# THS3201.net
KiCad netlist of a schematic drawn in Altium Designer
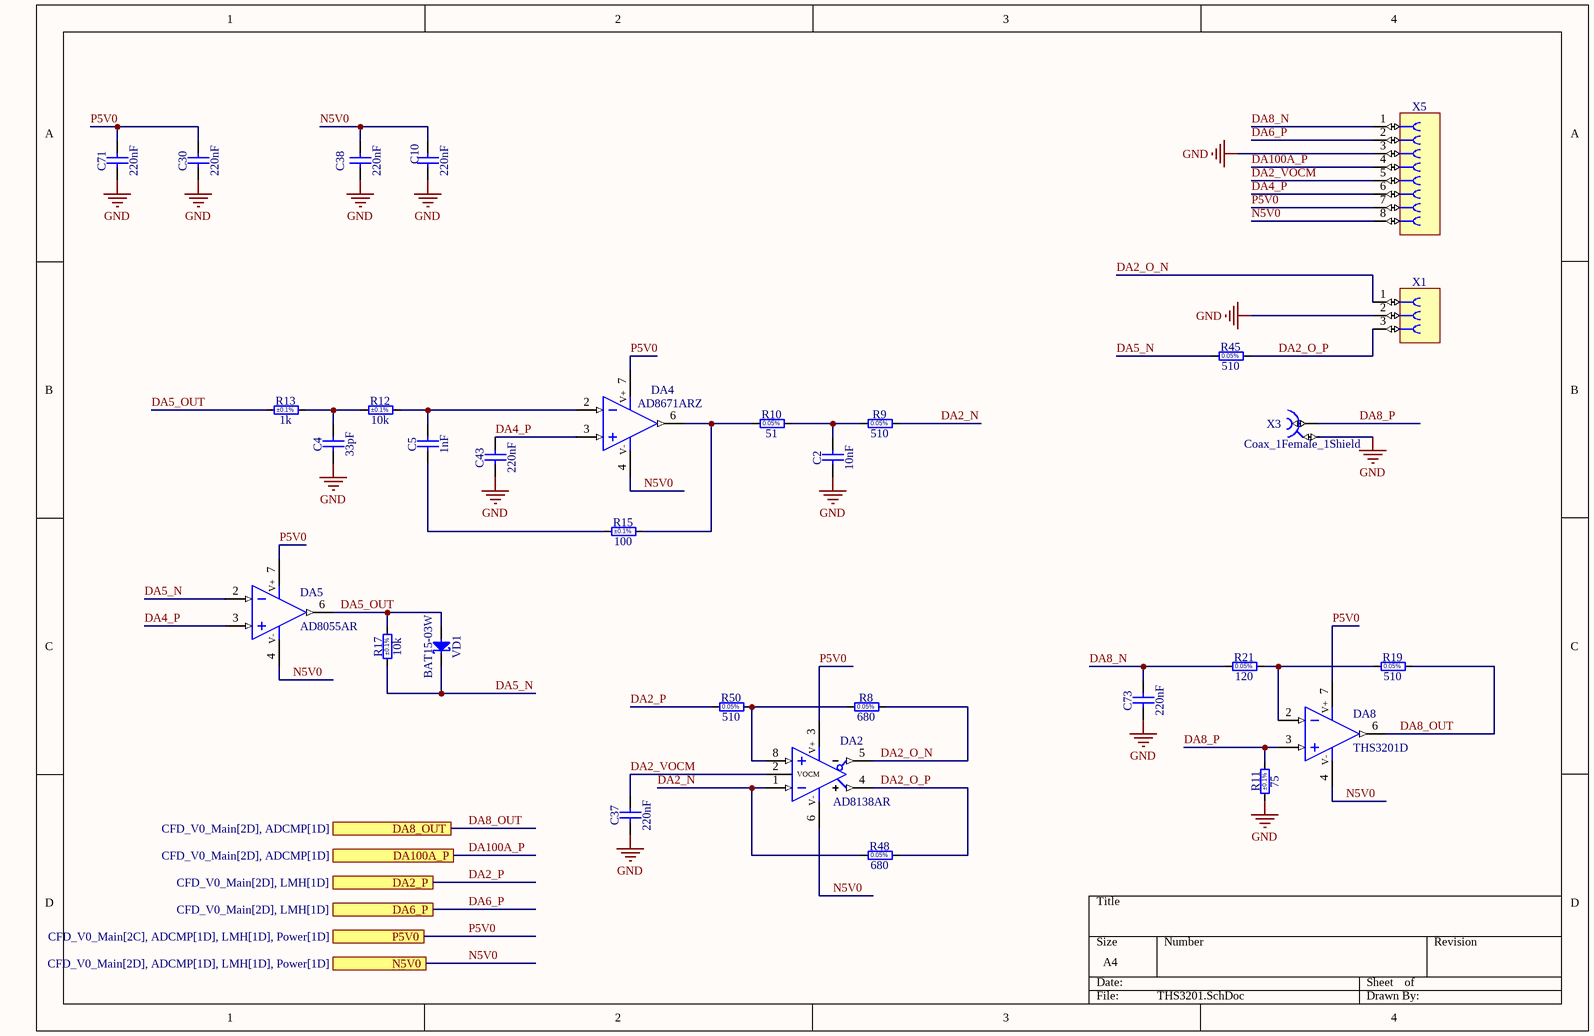
[diagram p0: THS3201.SchDoc]

(export (version "E")
  (design (tool "Eeschema 10.0.6"))
  (components
    (comp (ref "C2")
      (value "10nF")
      (footprint "CAPC2012X135N")
      (description "Non-polarised capacitor")
      (fields
        (field (name "PART NUMBER") "CC0805_10NF_50V_2%_C0G")
        (field (name "VOLTAGE") "50V")
        (field (name "AUTHOR") "CERN DEM HF")
      )
      (libsource (lib "Capacitors") (part "Capacitor - non polarized"))
    )
    (comp (ref "C4")
      (value "33pF")
      (footprint "CAPC2013X115N")
      (description "Non-polarised capacitor")
      (fields
        (field (name "PART NUMBER") "CC0805_33PF_200V_1%_NP0")
        (field (name "VOLTAGE") "200V")
        (field (name "AUTHOR") "CERN DEM HF")
      )
      (libsource (lib "Capacitors") (part "Capacitor - non polarized"))
    )
    (comp (ref "C5")
      (value "1nF")
      (footprint "CAPC2013X100N")
      (description "Non-polarised capacitor")
      (fields
        (field (name "PART NUMBER") "CC0805_1NF_25V_1%_C0G")
        (field (name "VOLTAGE") "25V")
        (field (name "AUTHOR") "CERN DEM JLC")
      )
      (libsource (lib "Capacitors") (part "Capacitor - non polarized"))
    )
    (comp (ref "C10")
      (value "220nF")
      (footprint "CAPC2012X135N")
      (description "Non-polarised capacitor")
      (fields
        (field (name "PART NUMBER") "CC0805_220NF_50V_10%_X7R")
        (field (name "VOLTAGE") "50V")
        (field (name "AUTHOR") "CERN DEM JLC")
      )
      (libsource (lib "Capacitors") (part "Capacitor - non polarized"))
    )
    (comp (ref "C30")
      (value "220nF")
      (footprint "CAPC2012X135N")
      (description "Non-polarised capacitor")
      (fields
        (field (name "PART NUMBER") "CC0805_220NF_50V_10%_X7R")
        (field (name "VOLTAGE") "50V")
        (field (name "AUTHOR") "CERN DEM JLC")
      )
      (libsource (lib "Capacitors") (part "Capacitor - non polarized"))
    )
    (comp (ref "C37")
      (value "220nF")
      (footprint "CAPC2012X135N")
      (description "Non-polarised capacitor")
      (fields
        (field (name "PART NUMBER") "CC0805_220NF_50V_10%_X7R")
        (field (name "VOLTAGE") "50V")
        (field (name "AUTHOR") "CERN DEM JLC")
      )
      (libsource (lib "Capacitors") (part "Capacitor - non polarized"))
    )
    (comp (ref "C38")
      (value "220nF")
      (footprint "CAPC2012X135N")
      (description "Non-polarised capacitor")
      (fields
        (field (name "PART NUMBER") "CC0805_220NF_50V_10%_X7R")
        (field (name "VOLTAGE") "50V")
        (field (name "AUTHOR") "CERN DEM JLC")
      )
      (libsource (lib "Capacitors") (part "Capacitor - non polarized"))
    )
    (comp (ref "C43")
      (value "220nF")
      (footprint "CAPC2012X135N")
      (description "Non-polarised capacitor")
      (fields
        (field (name "PART NUMBER") "CC0805_220NF_50V_10%_X7R")
        (field (name "VOLTAGE") "50V")
        (field (name "AUTHOR") "CERN DEM JLC")
      )
      (libsource (lib "Capacitors") (part "Capacitor - non polarized"))
    )
    (comp (ref "C71")
      (value "220nF")
      (footprint "CAPC2012X135N")
      (description "Non-polarised capacitor")
      (fields
        (field (name "PART NUMBER") "CC0805_220NF_50V_10%_X7R")
        (field (name "VOLTAGE") "50V")
        (field (name "AUTHOR") "CERN DEM JLC")
      )
      (libsource (lib "Capacitors") (part "Capacitor - non polarized"))
    )
    (comp (ref "C73")
      (value "220nF")
      (footprint "CAPC2012X135N")
      (description "Non-polarised capacitor")
      (fields
        (field (name "PART NUMBER") "CC0805_220NF_50V_10%_X7R")
        (field (name "VOLTAGE") "50V")
        (field (name "AUTHOR") "CERN DEM JLC")
      )
      (libsource (lib "Capacitors") (part "Capacitor - non polarized"))
    )
    (comp (ref "DA2")
      (value "AD8138AR")
      (footprint "SOIC127P600X175-8N")
      (description "Differential Amplifier")
      (fields (field (name "MANUFACTURER") "ANALOG DEVICES") (field (name "AUTHOR") "CERN DEM JLC"))
      (libsource (lib "ICs And Semiconductors") (part "Differential Amplifier Type1"))
    )
    (comp (ref "DA4")
      (value "AD8671ARZ")
      (footprint "SOIC127P600X175-8N")
      (description "Operational Amplifier")
      (fields
        (field (name "MANUFACTURER") "ANALOG DEVICES")
        (field (name "MANUFACTURER PART NUMBER") "AD8671AR")
        (field (name "AUTHOR") "CERN DEM JLC")
      )
      (libsource (lib "ICs And Semiconductors") (part "Operational Amplifier Type1"))
    )
    (comp (ref "DA5")
      (value "AD8055AR")
      (footprint "SOIC127P600X175-8N")
      (description "Operational Amplifier")
      (fields (field (name "MANUFACTURER") "ANALOG DEVICES") (field (name "AUTHOR") "CERN DEM HF"))
      (libsource (lib "ICs And Semiconductors") (part "Operational Amplifier Type1"))
    )
    (comp (ref "DA8")
      (value "THS3201D")
      (footprint "SOIC127P600X175-8N")
      (description "Operational Amplifier")
      (fields (field (name "MANUFACTURER") "TEXAS INSTRUMENTS") (field (name "AUTHOR") "CERN DEM HF"))
      (libsource (lib "ICs And Semiconductors") (part "Operational Amplifier Type1"))
    )
    (comp (ref "R8")
      (value "680")
      (footprint "RESC2012X60N")
      (description "Resistor - 0.05%")
      (fields
        (field (name "PART NUMBER") "R0805_680R_0.05%_0.125W_10PPM")
        (field (name "POWER") "0.1W")
        (field (name "AUTHOR") "CERN DEM HF")
      )
      (libsource (lib "Resistors") (part "Resistor - 0.05%"))
    )
    (comp (ref "R9")
      (value "510")
      (footprint "RESC1608X55N")
      (description "Resistor - 0.05%")
      (fields
        (field (name "PART NUMBER") "R0603_510R_0.1%_0.1W_10PPM")
        (field (name "POWER") "0.1W")
        (field (name "AUTHOR") "CERN DEM HF")
      )
      (libsource (lib "Resistors") (part "Resistor - 0.05%"))
    )
    (comp (ref "R10")
      (value "51")
      (footprint "RESC2012X60N")
      (description "Resistor - 0.05%")
      (fields
        (field (name "PART NUMBER") "R0805_51R_0.05%_0.125W_10PPM")
        (field (name "POWER") "0.1W")
        (field (name "AUTHOR") "CERN DEM HF")
      )
      (libsource (lib "Resistors") (part "Resistor - 0.05%"))
    )
    (comp (ref "R11")
      (value "75")
      (footprint "RESC1608X55N")
      (description "Resistor - 0.1%")
      (fields
        (field (name "TOLERANCE") "±0.1%")
        (field (name "PART NUMBER") "R0603_75R_0.1%_0.063W_10PPM")
        (field (name "POWER") "0.063W")
        (field (name "AUTHOR") "CERN DEM JLC")
      )
      (libsource (lib "Resistors") (part "Resistor - 0.1%"))
    )
    (comp (ref "R12")
      (value "10k")
      (footprint "RESC2012X60N")
      (description "Resistor - 0.1%")
      (fields
        (field (name "TOLERANCE") "±0.1%")
        (field (name "PART NUMBER") "R0805_10K_0.1%_0.1W_10PPM")
        (field (name "POWER") "0.1W")
        (field (name "AUTHOR") "CERN DEM JLC")
      )
      (libsource (lib "Resistors") (part "Resistor - 0.1%"))
    )
    (comp (ref "R13")
      (value "1k")
      (footprint "RESC2012X60N")
      (description "Resistor - 0.1%")
      (fields
        (field (name "TOLERANCE") "±0.1%")
        (field (name "PART NUMBER") "R0805_1K_0.1%_0.1W_10PPM")
        (field (name "POWER") "0.1W")
        (field (name "AUTHOR") "CERN DEM JLC")
      )
      (libsource (lib "Resistors") (part "Resistor - 0.1%"))
    )
    (comp (ref "R15")
      (value "100")
      (footprint "RESC2012X60N")
      (description "Resistor - 0.1%")
      (fields
        (field (name "TOLERANCE") "±0.1%")
        (field (name "PART NUMBER") "R0805_100R_0.1%_0.1W_10PPM")
        (field (name "POWER") "0.1W")
        (field (name "AUTHOR") "CERN DEM JLC")
      )
      (libsource (lib "Resistors") (part "Resistor - 0.1%"))
    )
    (comp (ref "R17")
      (value "10k")
      (footprint "RESC2012X60N")
      (description "Resistor - 0.1%")
      (fields
        (field (name "TOLERANCE") "±0.1%")
        (field (name "PART NUMBER") "R0805_10K_0.1%_0.1W_10PPM")
        (field (name "POWER") "0.1W")
        (field (name "AUTHOR") "CERN DEM JLC")
      )
      (libsource (lib "Resistors") (part "Resistor - 0.1%"))
    )
    (comp (ref "R19")
      (value "510")
      (footprint "RESC1608X55N")
      (description "Resistor - 0.05%")
      (fields
        (field (name "PART NUMBER") "R0603_510R_0.1%_0.1W_10PPM")
        (field (name "POWER") "0.1W")
        (field (name "AUTHOR") "CERN DEM HF")
      )
      (libsource (lib "Resistors") (part "Resistor - 0.05%"))
    )
    (comp (ref "R21")
      (value "120")
      (footprint "RESC1608X55N")
      (description "Resistor - 0.05%")
      (fields
        (field (name "PART NUMBER") "R0603_120R_0.05%_0.1W_10PPM")
        (field (name "POWER") "0.1W")
        (field (name "AUTHOR") "CERN DEM HF")
      )
      (libsource (lib "Resistors") (part "Resistor - 0.05%"))
    )
    (comp (ref "R45")
      (value "510")
      (footprint "RESC1608X55N")
      (description "Resistor - 0.05%")
      (fields
        (field (name "PART NUMBER") "R0603_510R_0.1%_0.1W_10PPM")
        (field (name "POWER") "0.1W")
        (field (name "AUTHOR") "CERN DEM HF")
      )
      (libsource (lib "Resistors") (part "Resistor - 0.05%"))
    )
    (comp (ref "R48")
      (value "680")
      (footprint "RESC2012X60N")
      (description "Resistor - 0.05%")
      (fields
        (field (name "PART NUMBER") "R0805_680R_0.05%_0.125W_10PPM")
        (field (name "POWER") "0.1W")
        (field (name "AUTHOR") "CERN DEM HF")
      )
      (libsource (lib "Resistors") (part "Resistor - 0.05%"))
    )
    (comp (ref "R50")
      (value "510")
      (footprint "RESC1608X55N")
      (description "Resistor - 0.05%")
      (fields
        (field (name "PART NUMBER") "R0603_510R_0.1%_0.1W_10PPM")
        (field (name "POWER") "0.1W")
        (field (name "AUTHOR") "CERN DEM HF")
      )
      (libsource (lib "Resistors") (part "Resistor - 0.05%"))
    )
    (comp (ref "VD1")
      (value "BAT15-03W")
      (footprint "SOD2512X110N")
      (description "Schottky Diode")
      (fields
        (field (name "VOLTAGE") "4V")
        (field (name "POWER") "100mA")
        (field (name "AUTHOR") "CERN DEM HF")
      )
      (libsource (lib "ICs And Semiconductors") (part "Diode Schottky"))
    )
    (comp (ref "X1")
      (value "Socket 3")
      (footprint "SAMTEC_CES-103-01-T-S")
      (description "Connector 3 Female")
      (fields
        (field (name "PART NUMBER") "SAMTEC_CES-103-01-L-S")
        (field (name "MANUFACTURER") "SAMTEC")
        (field (name "AUTHOR") "CERN DEM HF")
      )
      (libsource (lib "Connectors") (part "Connector 3 Female"))
    )
    (comp (ref "X3")
      (value "Coax_1Female_1Shield")
      (footprint "SAMTEC_MMCX-J-P-H-ST-TH1")
      (fields
        (field (name "PART NUMBER") "SAMTEC_MMCX-J-P-H-ST-TH1")
        (field (name "MANUFACTURER") "SAMTEC")
        (field (name "MANUFACTURER PART NUMBER") "MMCX-J-P-H-ST-TH1")
        (field (name "AUTHOR") "CERN DEM JLC")
      )
      (libsource (lib "Connectors") (part "Coax_1Female_1Shield"))
    )
    (comp (ref "X5")
      (value "Socket 8")
      (footprint "SAMTEC_CES-108-01-T-S")
      (description "Connector 8 Female")
      (fields
        (field (name "PART NUMBER") "SAMTEC_CES-108-01-L-S")
        (field (name "MANUFACTURER") "SAMTEC")
        (field (name "AUTHOR") "CERN DEM HF")
      )
      (libsource (lib "Connectors") (part "Connector 8 Female"))
    )
  )
  (nets
    (net (code "1") (name "/DA2_N") (class "Default")
      (node (ref "DA2") (pin "1") (pinfunction "IN-_1") (pintype "input"))
      (node (ref "R48") (pin "1") (pinfunction "1_1") (pintype "passive"))
      (node (ref "R9") (pin "2") (pinfunction "2_2") (pintype "passive"))
    )
    (net (code "2") (name "/DA2_O_N") (class "Default")
      (node (ref "DA2") (pin "5") (pinfunction "VOUT-_5") (pintype "output"))
      (node (ref "R8") (pin "2") (pinfunction "2_2") (pintype "passive"))
      (node (ref "X1") (pin "1") (pinfunction "1_1") (pintype "bidirectional"))
    )
    (net (code "3") (name "/DA2_O_P") (class "Default")
      (node (ref "DA2") (pin "4") (pinfunction "VOUT+_4") (pintype "output"))
      (node (ref "R45") (pin "2") (pinfunction "2_2") (pintype "passive"))
      (node (ref "R48") (pin "2") (pinfunction "2_2") (pintype "passive"))
      (node (ref "X1") (pin "3") (pinfunction "3_3") (pintype "bidirectional"))
    )
    (net (code "4") (name "/DA2_P") (class "Default")
      (node (ref "R50") (pin "1") (pinfunction "1_1") (pintype "passive"))
    )
    (net (code "5") (name "/DA2_VOCM") (class "Default")
      (node (ref "C37") (pin "2") (pinfunction "2_2") (pintype "passive"))
      (node (ref "DA2") (pin "2") (pinfunction "VOCM_2") (pintype "passive"))
      (node (ref "X5") (pin "5") (pinfunction "5_5") (pintype "bidirectional"))
    )
    (net (code "6") (name "/DA4_P") (class "Default")
      (node (ref "C43") (pin "2") (pinfunction "2_2") (pintype "passive"))
      (node (ref "DA4") (pin "3") (pinfunction "IN+_3") (pintype "input"))
      (node (ref "DA5") (pin "3") (pinfunction "IN+_3") (pintype "input"))
      (node (ref "X5") (pin "6") (pinfunction "6_6") (pintype "bidirectional"))
    )
    (net (code "7") (name "/DA5_N") (class "Default")
      (node (ref "DA5") (pin "2") (pinfunction "IN-_2") (pintype "input"))
      (node (ref "R17") (pin "1") (pinfunction "1_1") (pintype "passive"))
      (node (ref "R45") (pin "1") (pinfunction "1_1") (pintype "passive"))
      (node (ref "VD1") (pin "1") (pinfunction "C_1") (pintype "passive"))
    )
    (net (code "8") (name "/DA5_OUT") (class "Default")
      (node (ref "DA5") (pin "6") (pinfunction "OUT_6") (pintype "output"))
      (node (ref "R13") (pin "1") (pinfunction "1_1") (pintype "passive"))
      (node (ref "R17") (pin "2") (pinfunction "2_2") (pintype "passive"))
      (node (ref "VD1") (pin "2") (pinfunction "A_2") (pintype "passive"))
    )
    (net (code "9") (name "/DA6_P") (class "Default")
      (node (ref "X5") (pin "2") (pinfunction "2_2") (pintype "bidirectional"))
    )
    (net (code "10") (name "/DA8_N") (class "Default")
      (node (ref "C73") (pin "2") (pinfunction "2_2") (pintype "passive"))
      (node (ref "R21") (pin "1") (pinfunction "1_1") (pintype "passive"))
      (node (ref "X5") (pin "1") (pinfunction "1_1") (pintype "bidirectional"))
    )
    (net (code "11") (name "/DA8_OUT") (class "Default")
      (node (ref "DA8") (pin "6") (pinfunction "OUT_6") (pintype "output"))
      (node (ref "R19") (pin "2") (pinfunction "2_2") (pintype "passive"))
    )
    (net (code "12") (name "/DA8_P") (class "Default")
      (node (ref "DA8") (pin "3") (pinfunction "IN+_3") (pintype "input"))
      (node (ref "R11") (pin "2") (pinfunction "2_2") (pintype "passive"))
      (node (ref "X3") (pin "1") (pinfunction "1_1") (pintype "bidirectional"))
    )
    (net (code "13") (name "/DA100A_P") (class "Default")
      (node (ref "X5") (pin "4") (pinfunction "4_4") (pintype "bidirectional"))
    )
    (net (code "14") (name "/N5V0") (class "Default")
      (node (ref "C10") (pin "2") (pinfunction "2_2") (pintype "passive"))
      (node (ref "C38") (pin "2") (pinfunction "2_2") (pintype "passive"))
      (node (ref "DA2") (pin "6") (pinfunction "V-_6") (pintype "power_in"))
      (node (ref "DA4") (pin "4") (pinfunction "V-_4") (pintype "power_in"))
      (node (ref "DA5") (pin "4") (pinfunction "V-_4") (pintype "power_in"))
      (node (ref "DA8") (pin "4") (pinfunction "V-_4") (pintype "power_in"))
      (node (ref "X5") (pin "8") (pinfunction "8_8") (pintype "bidirectional"))
    )
    (net (code "15") (name "/P5V0") (class "Default")
      (node (ref "C30") (pin "2") (pinfunction "2_2") (pintype "passive"))
      (node (ref "C71") (pin "2") (pinfunction "2_2") (pintype "passive"))
      (node (ref "DA2") (pin "3") (pinfunction "V+_3") (pintype "power_in"))
      (node (ref "DA4") (pin "7") (pinfunction "V+_7") (pintype "power_in"))
      (node (ref "DA5") (pin "7") (pinfunction "V+_7") (pintype "power_in"))
      (node (ref "DA8") (pin "7") (pinfunction "V+_7") (pintype "power_in"))
      (node (ref "X5") (pin "7") (pinfunction "7_7") (pintype "bidirectional"))
    )
    (net (code "16") (name "GND") (class "Default")
      (node (ref "C10") (pin "1") (pinfunction "1_1") (pintype "passive"))
      (node (ref "C2") (pin "1") (pinfunction "1_1") (pintype "passive"))
      (node (ref "C30") (pin "1") (pinfunction "1_1") (pintype "passive"))
      (node (ref "C37") (pin "1") (pinfunction "1_1") (pintype "passive"))
      (node (ref "C38") (pin "1") (pinfunction "1_1") (pintype "passive"))
      (node (ref "C4") (pin "1") (pinfunction "1_1") (pintype "passive"))
      (node (ref "C43") (pin "1") (pinfunction "1_1") (pintype "passive"))
      (node (ref "C71") (pin "1") (pinfunction "1_1") (pintype "passive"))
      (node (ref "C73") (pin "1") (pinfunction "1_1") (pintype "passive"))
      (node (ref "R11") (pin "1") (pinfunction "1_1") (pintype "passive"))
      (node (ref "X1") (pin "2") (pinfunction "2_2") (pintype "bidirectional"))
      (node (ref "X3") (pin "2") (pinfunction "2_2") (pintype "bidirectional"))
      (node (ref "X5") (pin "3") (pinfunction "3_3") (pintype "bidirectional"))
    )
    (net (code "17") (name "Net-(C2-Pad2)") (class "Default")
      (node (ref "C2") (pin "2") (pinfunction "2_2") (pintype "passive"))
      (node (ref "R10") (pin "2") (pinfunction "2_2") (pintype "passive"))
      (node (ref "R9") (pin "1") (pinfunction "1_1") (pintype "passive"))
    )
    (net (code "18") (name "Net-(C4-Pad2)") (class "Default")
      (node (ref "C4") (pin "2") (pinfunction "2_2") (pintype "passive"))
      (node (ref "R12") (pin "1") (pinfunction "1_1") (pintype "passive"))
      (node (ref "R13") (pin "2") (pinfunction "2_2") (pintype "passive"))
    )
    (net (code "19") (name "Net-(C5-Pad1)") (class "Default")
      (node (ref "C5") (pin "1") (pinfunction "1_1") (pintype "passive"))
      (node (ref "R15") (pin "1") (pinfunction "1_1") (pintype "passive"))
    )
    (net (code "20") (name "Net-(DA2-IN+)") (class "Default")
      (node (ref "DA2") (pin "8") (pinfunction "IN+_8") (pintype "input"))
      (node (ref "R50") (pin "2") (pinfunction "2_2") (pintype "passive"))
      (node (ref "R8") (pin "1") (pinfunction "1_1") (pintype "passive"))
    )
    (net (code "21") (name "Net-(DA4-IN-)") (class "Default")
      (node (ref "C5") (pin "2") (pinfunction "2_2") (pintype "passive"))
      (node (ref "DA4") (pin "2") (pinfunction "IN-_2") (pintype "input"))
      (node (ref "R12") (pin "2") (pinfunction "2_2") (pintype "passive"))
    )
    (net (code "22") (name "Net-(DA4-OUT)") (class "Default")
      (node (ref "DA4") (pin "6") (pinfunction "OUT_6") (pintype "output"))
      (node (ref "R10") (pin "1") (pinfunction "1_1") (pintype "passive"))
      (node (ref "R15") (pin "2") (pinfunction "2_2") (pintype "passive"))
    )
    (net (code "23") (name "Net-(DA8-IN-)") (class "Default")
      (node (ref "DA8") (pin "2") (pinfunction "IN-_2") (pintype "input"))
      (node (ref "R19") (pin "1") (pinfunction "1_1") (pintype "passive"))
      (node (ref "R21") (pin "2") (pinfunction "2_2") (pintype "passive"))
    )
  )
)
